# Kintex7_disp_inout_hdmi.net
KiCad netlist of a schematic drawn in EAGLE
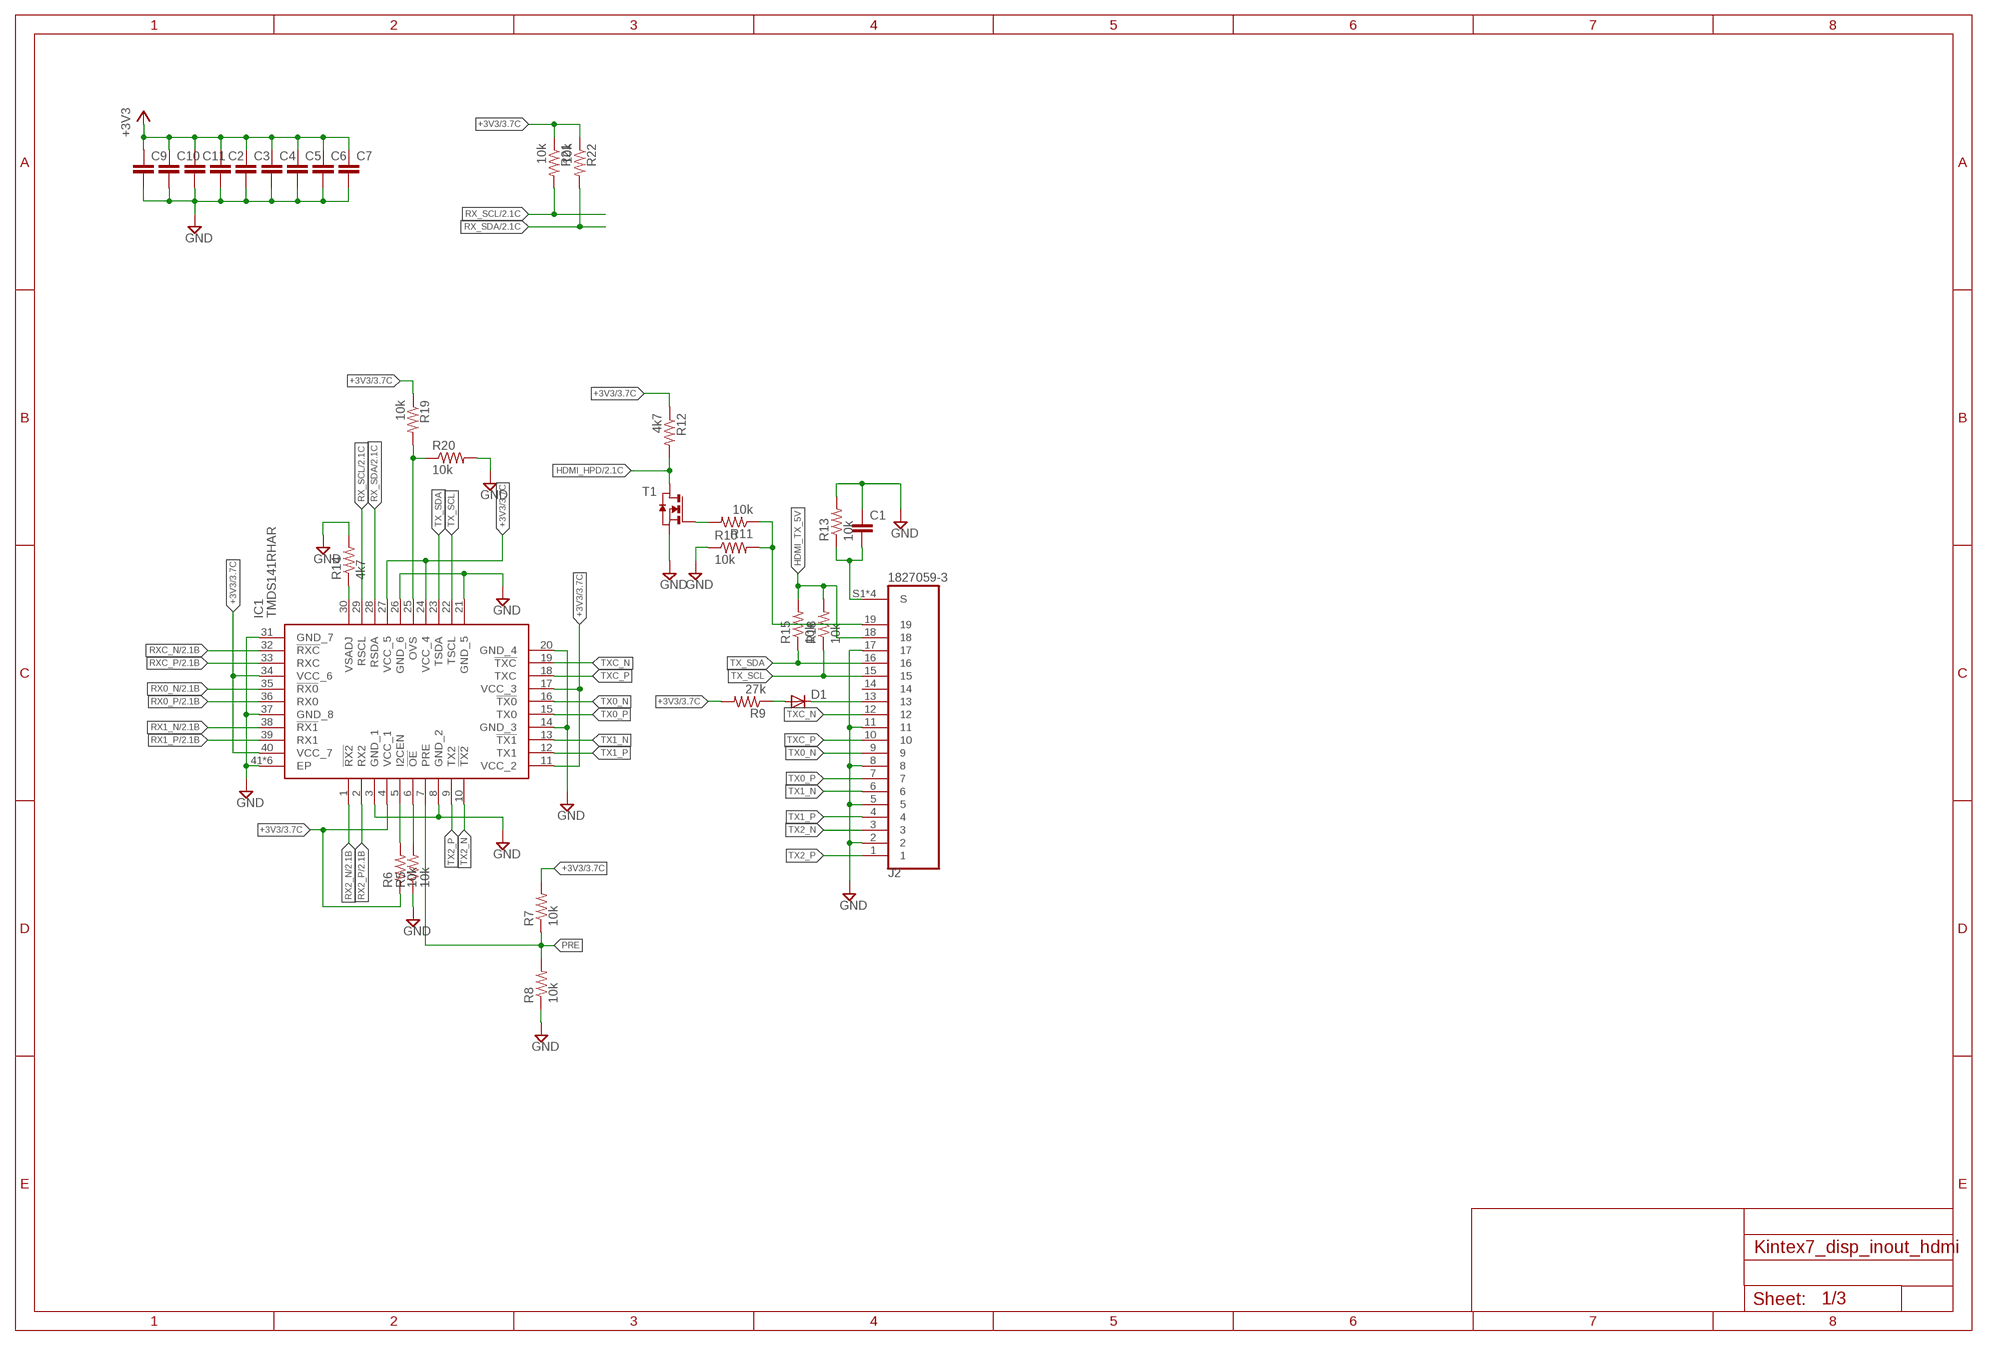
[diagram p0: schematic, sheet 1]
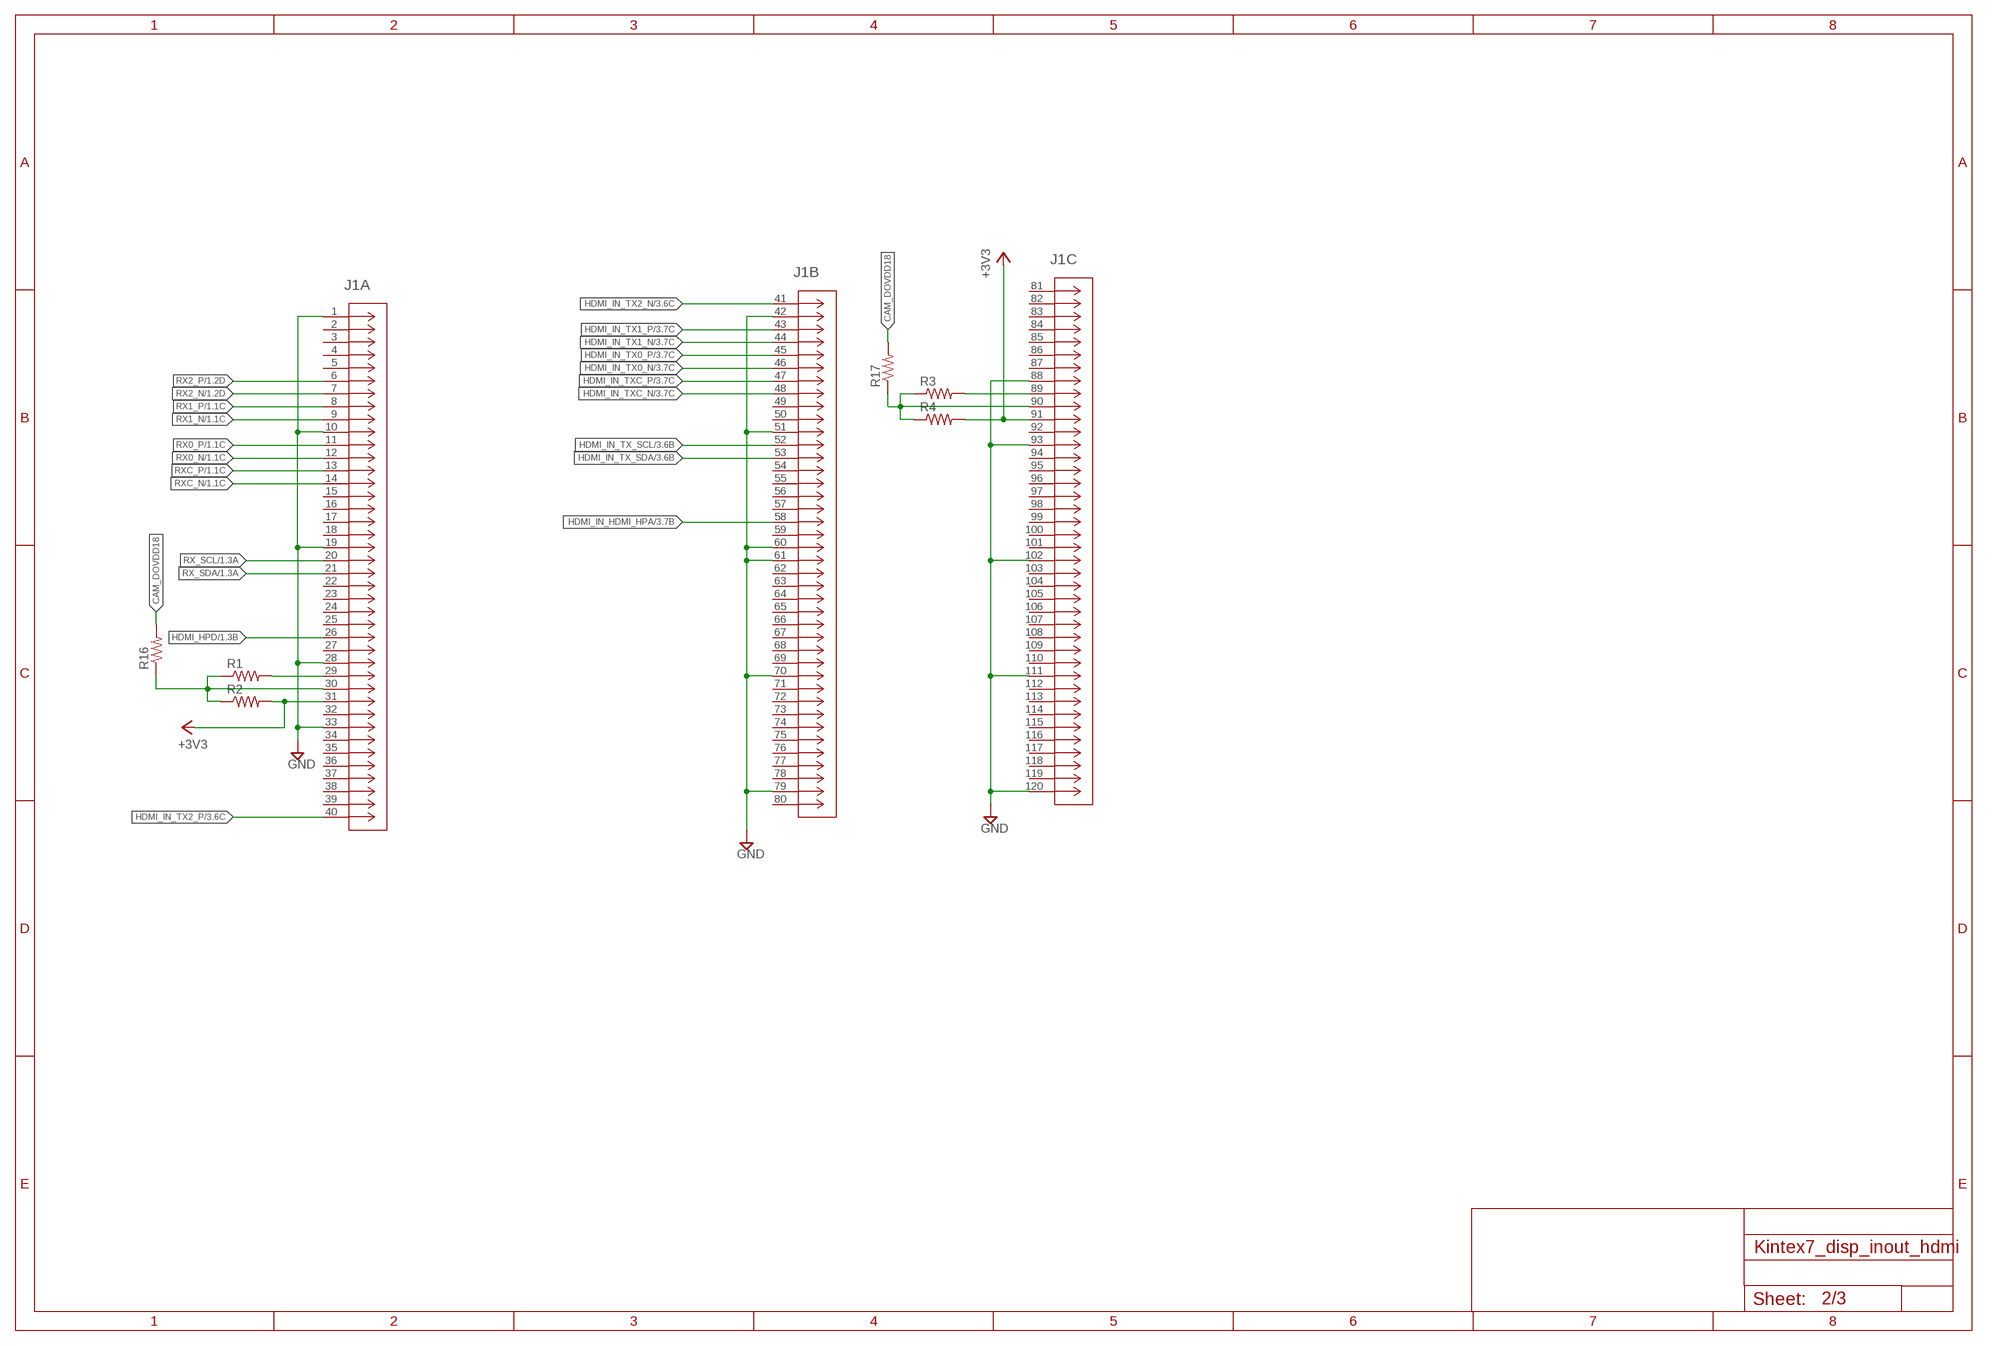
[diagram p1: schematic, sheet 2]
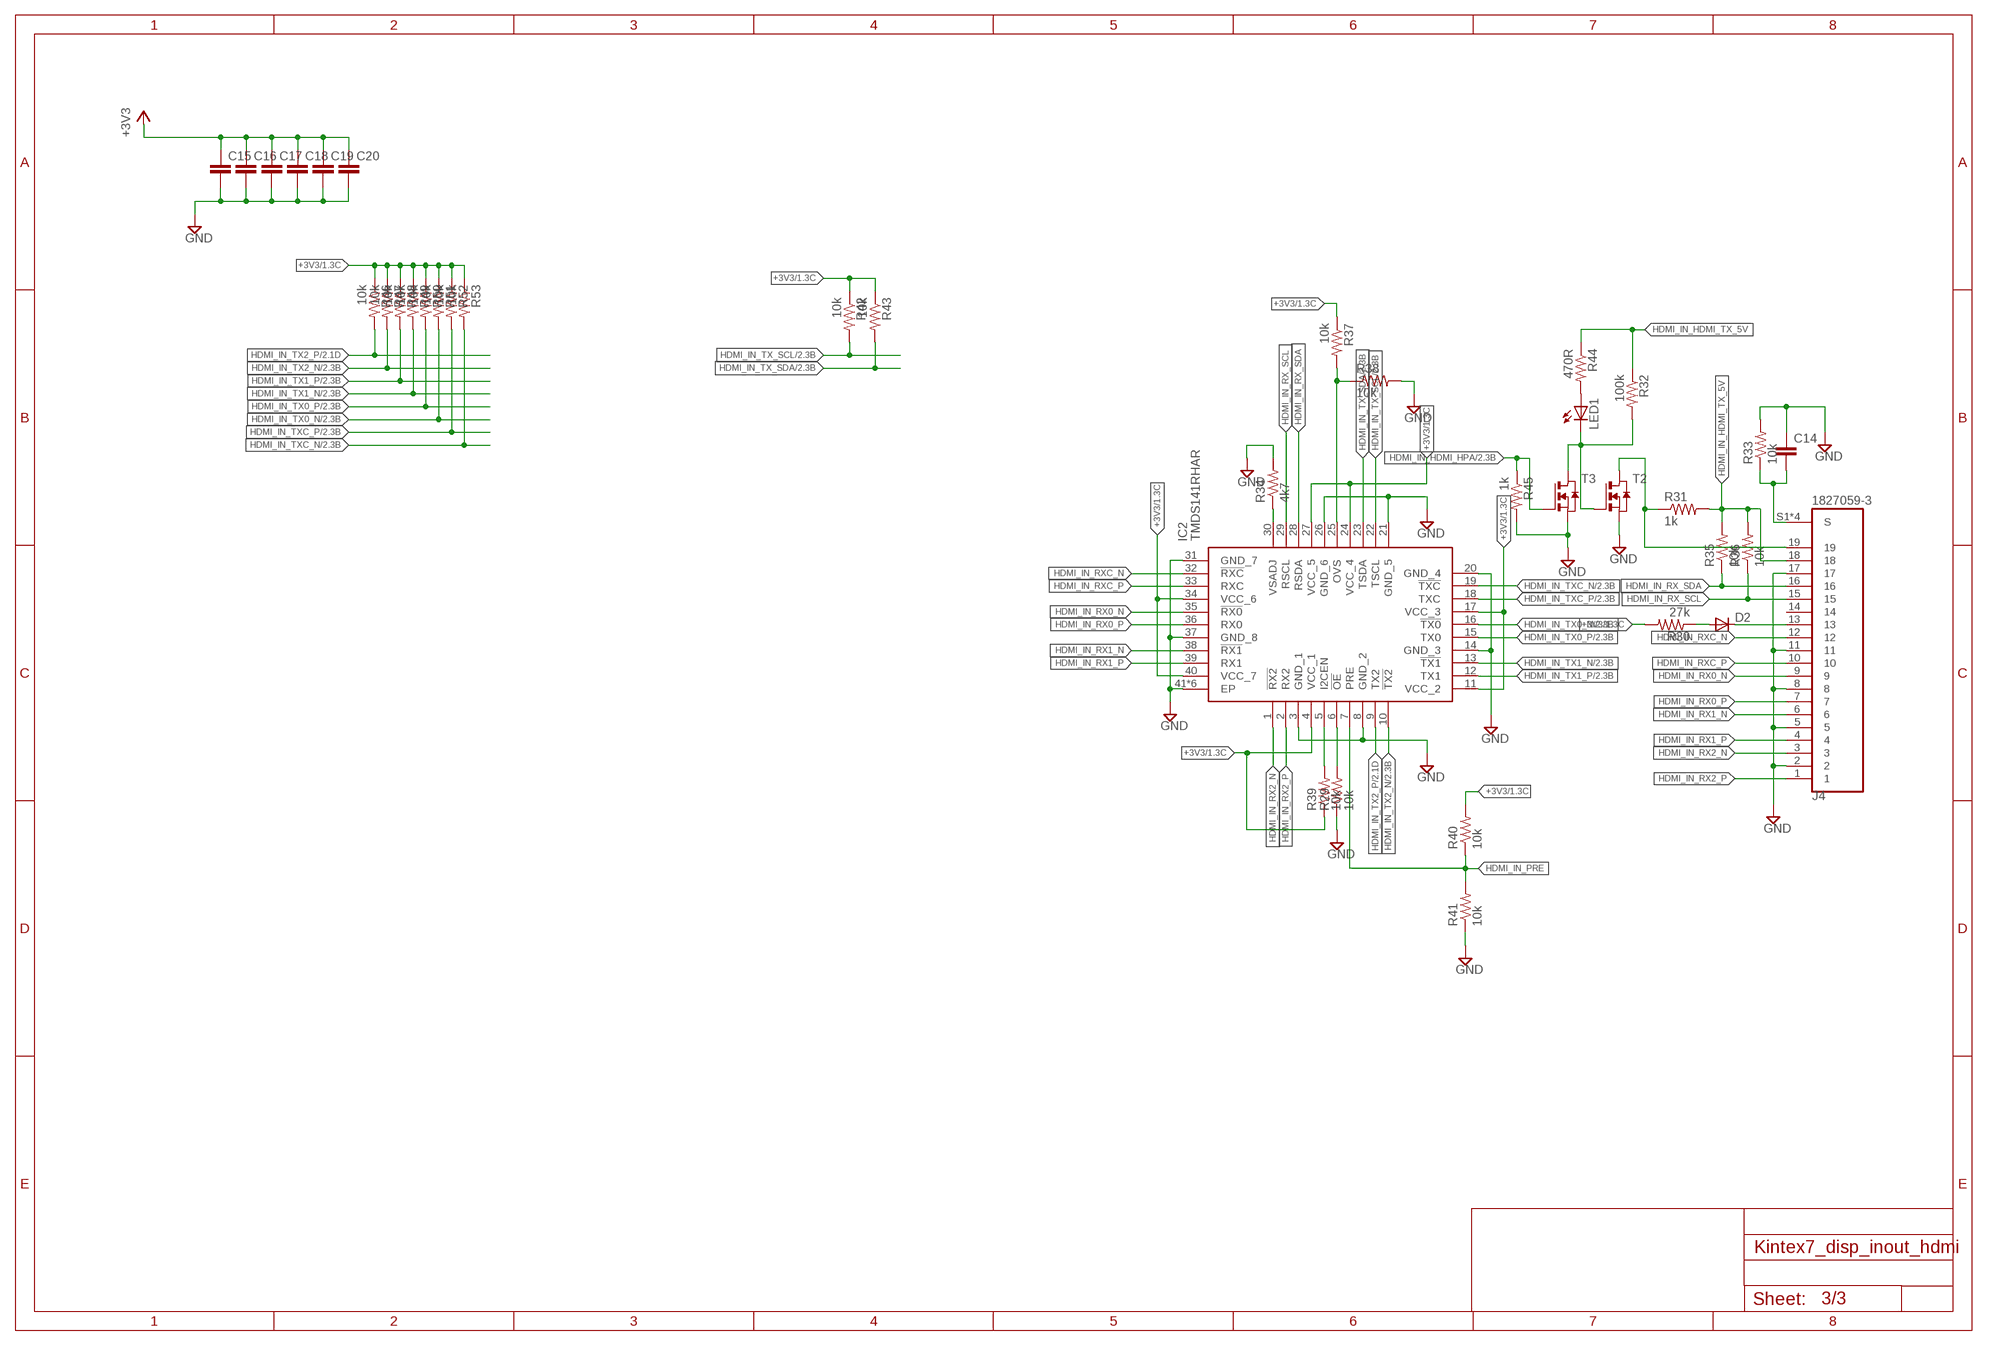
[diagram p2: schematic, sheet 3]

(export (version "E")
  (design (tool "Eeschema 10.0.6"))
  (components
    (comp (ref "C1")
      (value "C-EUC0603")
      (footprint "eagle-import:C0603")
      (libsource (lib "eagle-import") (part "C-EUC0603"))
    )
    (comp (ref "C2")
      (value "C-EUC0603")
      (footprint "eagle-import:C0603")
      (libsource (lib "eagle-import") (part "C-EUC0603"))
    )
    (comp (ref "C3")
      (value "C-EUC0603")
      (footprint "eagle-import:C0603")
      (libsource (lib "eagle-import") (part "C-EUC0603"))
    )
    (comp (ref "C4")
      (value "C-EUC0603")
      (footprint "eagle-import:C0603")
      (libsource (lib "eagle-import") (part "C-EUC0603"))
    )
    (comp (ref "C5")
      (value "C-EUC0603")
      (footprint "eagle-import:C0603")
      (libsource (lib "eagle-import") (part "C-EUC0603"))
    )
    (comp (ref "C6")
      (value "C-EUC0603")
      (footprint "eagle-import:C0603")
      (libsource (lib "eagle-import") (part "C-EUC0603"))
    )
    (comp (ref "C7")
      (value "C-EUC0603")
      (footprint "eagle-import:C0603")
      (libsource (lib "eagle-import") (part "C-EUC0603"))
    )
    (comp (ref "C9")
      (value "C-EUC0603")
      (footprint "eagle-import:C0603")
      (libsource (lib "eagle-import") (part "C-EUC0603"))
    )
    (comp (ref "C10")
      (value "C-EUC0603")
      (footprint "eagle-import:C0603")
      (libsource (lib "eagle-import") (part "C-EUC0603"))
    )
    (comp (ref "C11")
      (value "C-EUC0603")
      (footprint "eagle-import:C0603")
      (libsource (lib "eagle-import") (part "C-EUC0603"))
    )
    (comp (ref "D1")
      (value "DIODE-MINIMELF")
      (footprint "eagle-import:MINIMELF")
      (libsource (lib "eagle-import") (part "DIODE-MINIMELF"))
    )
    (comp (ref "IC1")
      (value "TMDS141RHAR")
      (footprint "eagle-import:QFN50P600X600X100-41N")
      (fields (field (name "RS_PART_NUMBER") "8124195P"))
      (libsource (lib "eagle-import") (part "TMDS141RHAR"))
    )
    (comp (ref "J2")
      (value "1827059-3")
      (footprint "eagle-import:TE_1827059-3")
      (fields (field (name "MF") "TE Connectivity"))
      (libsource (lib "eagle-import") (part "1827059-3"))
    )
    (comp (ref "R5")
      (value "10k")
      (footprint "eagle-import:R0805")
      (libsource (lib "eagle-import") (part "R-US_R0805"))
    )
    (comp (ref "R6")
      (value "10k")
      (footprint "eagle-import:R0805")
      (libsource (lib "eagle-import") (part "R-US_R0805"))
    )
    (comp (ref "R7")
      (value "10k")
      (footprint "eagle-import:R0805")
      (libsource (lib "eagle-import") (part "R-US_R0805"))
    )
    (comp (ref "R8")
      (value "10k")
      (footprint "eagle-import:R0805")
      (libsource (lib "eagle-import") (part "R-US_R0805"))
    )
    (comp (ref "R9")
      (value "27k")
      (footprint "eagle-import:R0805")
      (libsource (lib "eagle-import") (part "R-US_R0805"))
    )
    (comp (ref "R10")
      (value "10k")
      (footprint "eagle-import:R0805")
      (libsource (lib "eagle-import") (part "R-US_R0805"))
    )
    (comp (ref "R11")
      (value "10k")
      (footprint "eagle-import:R0805")
      (libsource (lib "eagle-import") (part "R-US_R0805"))
    )
    (comp (ref "R12")
      (value "4k7")
      (footprint "eagle-import:R0805")
      (libsource (lib "eagle-import") (part "R-US_R0805"))
    )
    (comp (ref "R13")
      (value "10k")
      (footprint "eagle-import:R0805")
      (libsource (lib "eagle-import") (part "R-US_R0805"))
    )
    (comp (ref "R14")
      (value "4k7")
      (footprint "eagle-import:R0805")
      (libsource (lib "eagle-import") (part "R-US_R0805"))
    )
    (comp (ref "R15")
      (value "10k")
      (footprint "eagle-import:R0805")
      (libsource (lib "eagle-import") (part "R-US_R0805"))
    )
    (comp (ref "R18")
      (value "10k")
      (footprint "eagle-import:R0805")
      (libsource (lib "eagle-import") (part "R-US_R0805"))
    )
    (comp (ref "R19")
      (value "10k")
      (footprint "eagle-import:R0805")
      (libsource (lib "eagle-import") (part "R-US_R0805"))
    )
    (comp (ref "R20")
      (value "10k")
      (footprint "eagle-import:R0805")
      (libsource (lib "eagle-import") (part "R-US_R0805"))
    )
    (comp (ref "R21")
      (value "10k")
      (footprint "eagle-import:R0805")
      (libsource (lib "eagle-import") (part "R-US_R0805"))
    )
    (comp (ref "R22")
      (value "10k")
      (footprint "eagle-import:R0805")
      (libsource (lib "eagle-import") (part "R-US_R0805"))
    )
    (comp (ref "T1")
      (value "NMOSSOT23")
      (footprint "eagle-import:SOT-23")
      (libsource (lib "eagle-import") (part "NMOSSOT23"))
    )
    (comp (ref "C14")
      (value "C-EUC0603")
      (footprint "eagle-import:C0603")
      (libsource (lib "eagle-import") (part "C-EUC0603"))
    )
    (comp (ref "C15")
      (value "C-EUC0603")
      (footprint "eagle-import:C0603")
      (libsource (lib "eagle-import") (part "C-EUC0603"))
    )
    (comp (ref "C16")
      (value "C-EUC0603")
      (footprint "eagle-import:C0603")
      (libsource (lib "eagle-import") (part "C-EUC0603"))
    )
    (comp (ref "C17")
      (value "C-EUC0603")
      (footprint "eagle-import:C0603")
      (libsource (lib "eagle-import") (part "C-EUC0603"))
    )
    (comp (ref "C18")
      (value "C-EUC0603")
      (footprint "eagle-import:C0603")
      (libsource (lib "eagle-import") (part "C-EUC0603"))
    )
    (comp (ref "C19")
      (value "C-EUC0603")
      (footprint "eagle-import:C0603")
      (libsource (lib "eagle-import") (part "C-EUC0603"))
    )
    (comp (ref "C20")
      (value "C-EUC0603")
      (footprint "eagle-import:C0603")
      (libsource (lib "eagle-import") (part "C-EUC0603"))
    )
    (comp (ref "D2")
      (value "DIODE-MINIMELF")
      (footprint "eagle-import:MINIMELF")
      (libsource (lib "eagle-import") (part "DIODE-MINIMELF"))
    )
    (comp (ref "IC2")
      (value "TMDS141RHAR")
      (footprint "eagle-import:QFN50P600X600X100-41N")
      (fields (field (name "RS_PART_NUMBER") "8124195P"))
      (libsource (lib "eagle-import") (part "TMDS141RHAR"))
    )
    (comp (ref "J4")
      (value "1827059-3")
      (footprint "eagle-import:TE_1827059-3")
      (fields (field (name "MF") "TE Connectivity"))
      (libsource (lib "eagle-import") (part "1827059-3"))
    )
    (comp (ref "LED1")
      (value "LEDCHIPLED_0603")
      (footprint "eagle-import:CHIPLED_0603")
      (libsource (lib "eagle-import") (part "LEDCHIPLED_0603"))
    )
    (comp (ref "R29")
      (value "10k")
      (footprint "eagle-import:R0805")
      (libsource (lib "eagle-import") (part "R-US_R0805"))
    )
    (comp (ref "R30")
      (value "27k")
      (footprint "eagle-import:R0805")
      (libsource (lib "eagle-import") (part "R-US_R0805"))
    )
    (comp (ref "R31")
      (value "1k")
      (footprint "eagle-import:R0805")
      (libsource (lib "eagle-import") (part "R-US_R0805"))
    )
    (comp (ref "R32")
      (value "100k")
      (footprint "eagle-import:R0805")
      (libsource (lib "eagle-import") (part "R-US_R0805"))
    )
    (comp (ref "R33")
      (value "10k")
      (footprint "eagle-import:R0805")
      (libsource (lib "eagle-import") (part "R-US_R0805"))
    )
    (comp (ref "R34")
      (value "4k7")
      (footprint "eagle-import:R0805")
      (libsource (lib "eagle-import") (part "R-US_R0805"))
    )
    (comp (ref "R35")
      (value "10k")
      (footprint "eagle-import:R0805")
      (libsource (lib "eagle-import") (part "R-US_R0805"))
    )
    (comp (ref "R36")
      (value "10k")
      (footprint "eagle-import:R0805")
      (libsource (lib "eagle-import") (part "R-US_R0805"))
    )
    (comp (ref "R37")
      (value "10k")
      (footprint "eagle-import:R0805")
      (libsource (lib "eagle-import") (part "R-US_R0805"))
    )
    (comp (ref "R38")
      (value "10k")
      (footprint "eagle-import:R0805")
      (libsource (lib "eagle-import") (part "R-US_R0805"))
    )
    (comp (ref "R39")
      (value "10k")
      (footprint "eagle-import:R0805")
      (libsource (lib "eagle-import") (part "R-US_R0805"))
    )
    (comp (ref "R40")
      (value "10k")
      (footprint "eagle-import:R0805")
      (libsource (lib "eagle-import") (part "R-US_R0805"))
    )
    (comp (ref "R41")
      (value "10k")
      (footprint "eagle-import:R0805")
      (libsource (lib "eagle-import") (part "R-US_R0805"))
    )
    (comp (ref "R42")
      (value "10k")
      (footprint "eagle-import:R0805")
      (libsource (lib "eagle-import") (part "R-US_R0805"))
    )
    (comp (ref "R43")
      (value "10k")
      (footprint "eagle-import:R0805")
      (libsource (lib "eagle-import") (part "R-US_R0805"))
    )
    (comp (ref "R44")
      (value "470R")
      (footprint "eagle-import:R0805")
      (libsource (lib "eagle-import") (part "R-US_R0805"))
    )
    (comp (ref "R45")
      (value "1k")
      (footprint "eagle-import:R0805")
      (libsource (lib "eagle-import") (part "R-US_R0805"))
    )
    (comp (ref "R46")
      (value "10k")
      (footprint "eagle-import:R0805")
      (libsource (lib "eagle-import") (part "R-US_R0805"))
    )
    (comp (ref "R47")
      (value "10k")
      (footprint "eagle-import:R0805")
      (libsource (lib "eagle-import") (part "R-US_R0805"))
    )
    (comp (ref "R48")
      (value "10k")
      (footprint "eagle-import:R0805")
      (libsource (lib "eagle-import") (part "R-US_R0805"))
    )
    (comp (ref "R49")
      (value "10k")
      (footprint "eagle-import:R0805")
      (libsource (lib "eagle-import") (part "R-US_R0805"))
    )
    (comp (ref "R50")
      (value "10k")
      (footprint "eagle-import:R0805")
      (libsource (lib "eagle-import") (part "R-US_R0805"))
    )
    (comp (ref "R51")
      (value "10k")
      (footprint "eagle-import:R0805")
      (libsource (lib "eagle-import") (part "R-US_R0805"))
    )
    (comp (ref "R52")
      (value "10k")
      (footprint "eagle-import:R0805")
      (libsource (lib "eagle-import") (part "R-US_R0805"))
    )
    (comp (ref "R53")
      (value "10k")
      (footprint "eagle-import:R0805")
      (libsource (lib "eagle-import") (part "R-US_R0805"))
    )
    (comp (ref "T2")
      (value "NMOSSOT23")
      (footprint "eagle-import:SOT-23")
      (libsource (lib "eagle-import") (part "NMOSSOT23"))
    )
    (comp (ref "T3")
      (value "NMOSSOT23")
      (footprint "eagle-import:SOT-23")
      (libsource (lib "eagle-import") (part "NMOSSOT23"))
    )
    (comp (ref "J1")
      (value "5177985-5")
      (footprint "eagle-import:CONN_5177985-5")
      (libsource (lib "eagle-import") (part "5177985-5"))
    )
    (comp (ref "R1")
      (value "R-US_R0805")
      (footprint "eagle-import:R0805")
      (libsource (lib "eagle-import") (part "R-US_R0805"))
    )
    (comp (ref "R2")
      (value "R-US_R0805")
      (footprint "eagle-import:R0805")
      (libsource (lib "eagle-import") (part "R-US_R0805"))
    )
    (comp (ref "R3")
      (value "R-US_R0805")
      (footprint "eagle-import:R0805")
      (libsource (lib "eagle-import") (part "R-US_R0805"))
    )
    (comp (ref "R4")
      (value "R-US_R0805")
      (footprint "eagle-import:R0805")
      (libsource (lib "eagle-import") (part "R-US_R0805"))
    )
    (comp (ref "R16")
      (value "R-US_R0805")
      (footprint "eagle-import:R0805")
      (libsource (lib "eagle-import") (part "R-US_R0805"))
    )
    (comp (ref "R17")
      (value "R-US_R0805")
      (footprint "eagle-import:R0805")
      (libsource (lib "eagle-import") (part "R-US_R0805"))
    )
  )
  (nets
    (net (code "1") (name "+3V3") (class "Default")
      (node (ref "C10") (pin "1") (pinfunction "1_1") (pintype "passive"))
      (node (ref "C11") (pin "1") (pinfunction "1_1") (pintype "passive"))
      (node (ref "C15") (pin "1") (pinfunction "1_1") (pintype "passive"))
      (node (ref "C16") (pin "1") (pinfunction "1_1") (pintype "passive"))
      (node (ref "C17") (pin "1") (pinfunction "1_1") (pintype "passive"))
      (node (ref "C18") (pin "1") (pinfunction "1_1") (pintype "passive"))
      (node (ref "C19") (pin "1") (pinfunction "1_1") (pintype "passive"))
      (node (ref "C2") (pin "1") (pinfunction "1_1") (pintype "passive"))
      (node (ref "C20") (pin "1") (pinfunction "1_1") (pintype "passive"))
      (node (ref "C3") (pin "1") (pinfunction "1_1") (pintype "passive"))
      (node (ref "C4") (pin "1") (pinfunction "1_1") (pintype "passive"))
      (node (ref "C5") (pin "1") (pinfunction "1_1") (pintype "passive"))
      (node (ref "C6") (pin "1") (pinfunction "1_1") (pintype "passive"))
      (node (ref "C7") (pin "1") (pinfunction "1_1") (pintype "passive"))
      (node (ref "C9") (pin "1") (pinfunction "1_1") (pintype "passive"))
      (node (ref "IC1") (pin "11") (pinfunction "VCC_2_11") (pintype "bidirectional"))
      (node (ref "IC1") (pin "17") (pinfunction "VCC_3_17") (pintype "bidirectional"))
      (node (ref "IC1") (pin "24") (pinfunction "VCC_4_24") (pintype "bidirectional"))
      (node (ref "IC1") (pin "27") (pinfunction "VCC_5_27") (pintype "bidirectional"))
      (node (ref "IC1") (pin "34") (pinfunction "VCC_6_34") (pintype "bidirectional"))
      (node (ref "IC1") (pin "4") (pinfunction "VCC_1_4") (pintype "bidirectional"))
      (node (ref "IC1") (pin "40") (pinfunction "VCC_7_40") (pintype "bidirectional"))
      (node (ref "IC2") (pin "11") (pinfunction "VCC_2_11") (pintype "bidirectional"))
      (node (ref "IC2") (pin "17") (pinfunction "VCC_3_17") (pintype "bidirectional"))
      (node (ref "IC2") (pin "24") (pinfunction "VCC_4_24") (pintype "bidirectional"))
      (node (ref "IC2") (pin "27") (pinfunction "VCC_5_27") (pintype "bidirectional"))
      (node (ref "IC2") (pin "34") (pinfunction "VCC_6_34") (pintype "bidirectional"))
      (node (ref "IC2") (pin "4") (pinfunction "VCC_1_4") (pintype "bidirectional"))
      (node (ref "IC2") (pin "40") (pinfunction "VCC_7_40") (pintype "bidirectional"))
      (node (ref "J1") (pin "31") (pinfunction "31_31") (pintype "passive"))
      (node (ref "J1") (pin "91") (pinfunction "91_91") (pintype "passive"))
      (node (ref "R12") (pin "1") (pinfunction "1_1") (pintype "passive"))
      (node (ref "R19") (pin "1") (pinfunction "1_1") (pintype "passive"))
      (node (ref "R2") (pin "2") (pinfunction "2_2") (pintype "passive"))
      (node (ref "R21") (pin "1") (pinfunction "1_1") (pintype "passive"))
      (node (ref "R22") (pin "1") (pinfunction "1_1") (pintype "passive"))
      (node (ref "R30") (pin "2") (pinfunction "2_2") (pintype "passive"))
      (node (ref "R37") (pin "1") (pinfunction "1_1") (pintype "passive"))
      (node (ref "R39") (pin "1") (pinfunction "1_1") (pintype "passive"))
      (node (ref "R4") (pin "2") (pinfunction "2_2") (pintype "passive"))
      (node (ref "R40") (pin "2") (pinfunction "2_2") (pintype "passive"))
      (node (ref "R42") (pin "1") (pinfunction "1_1") (pintype "passive"))
      (node (ref "R43") (pin "1") (pinfunction "1_1") (pintype "passive"))
      (node (ref "R46") (pin "1") (pinfunction "1_1") (pintype "passive"))
      (node (ref "R47") (pin "1") (pinfunction "1_1") (pintype "passive"))
      (node (ref "R48") (pin "1") (pinfunction "1_1") (pintype "passive"))
      (node (ref "R49") (pin "1") (pinfunction "1_1") (pintype "passive"))
      (node (ref "R50") (pin "1") (pinfunction "1_1") (pintype "passive"))
      (node (ref "R51") (pin "1") (pinfunction "1_1") (pintype "passive"))
      (node (ref "R52") (pin "1") (pinfunction "1_1") (pintype "passive"))
      (node (ref "R53") (pin "1") (pinfunction "1_1") (pintype "passive"))
      (node (ref "R6") (pin "1") (pinfunction "1_1") (pintype "passive"))
      (node (ref "R7") (pin "2") (pinfunction "2_2") (pintype "passive"))
      (node (ref "R9") (pin "2") (pinfunction "2_2") (pintype "passive"))
    )
    (net (code "2") (name "CAM_DOVDD18") (class "Default")
      (node (ref "R16") (pin "2") (pinfunction "2_2") (pintype "passive"))
      (node (ref "R17") (pin "2") (pinfunction "2_2") (pintype "passive"))
    )
    (net (code "3") (name "GND") (class "Default")
      (node (ref "C1") (pin "1") (pinfunction "1_1") (pintype "passive"))
      (node (ref "C10") (pin "2") (pinfunction "2_2") (pintype "passive"))
      (node (ref "C11") (pin "2") (pinfunction "2_2") (pintype "passive"))
      (node (ref "C14") (pin "1") (pinfunction "1_1") (pintype "passive"))
      (node (ref "C15") (pin "2") (pinfunction "2_2") (pintype "passive"))
      (node (ref "C16") (pin "2") (pinfunction "2_2") (pintype "passive"))
      (node (ref "C17") (pin "2") (pinfunction "2_2") (pintype "passive"))
      (node (ref "C18") (pin "2") (pinfunction "2_2") (pintype "passive"))
      (node (ref "C19") (pin "2") (pinfunction "2_2") (pintype "passive"))
      (node (ref "C2") (pin "2") (pinfunction "2_2") (pintype "passive"))
      (node (ref "C20") (pin "2") (pinfunction "2_2") (pintype "passive"))
      (node (ref "C3") (pin "2") (pinfunction "2_2") (pintype "passive"))
      (node (ref "C4") (pin "2") (pinfunction "2_2") (pintype "passive"))
      (node (ref "C5") (pin "2") (pinfunction "2_2") (pintype "passive"))
      (node (ref "C6") (pin "2") (pinfunction "2_2") (pintype "passive"))
      (node (ref "C7") (pin "2") (pinfunction "2_2") (pintype "passive"))
      (node (ref "C9") (pin "2") (pinfunction "2_2") (pintype "passive"))
      (node (ref "IC1") (pin "14") (pinfunction "GND_3_14") (pintype "bidirectional"))
      (node (ref "IC1") (pin "20") (pinfunction "GND_4_20") (pintype "bidirectional"))
      (node (ref "IC1") (pin "21") (pinfunction "GND_5_21") (pintype "bidirectional"))
      (node (ref "IC1") (pin "26") (pinfunction "GND_6_26") (pintype "bidirectional"))
      (node (ref "IC1") (pin "3") (pinfunction "GND_1_3") (pintype "bidirectional"))
      (node (ref "IC1") (pin "31") (pinfunction "GND_7_31") (pintype "bidirectional"))
      (node (ref "IC1") (pin "37") (pinfunction "GND_8_37") (pintype "bidirectional"))
      (node (ref "IC1") (pin "41") (pinfunction "EP_41") (pintype "bidirectional"))
      (node (ref "IC1") (pin "8") (pinfunction "GND_2_8") (pintype "bidirectional"))
      (node (ref "IC1") (pin "P$1") (pinfunction "EP_P$1") (pintype "bidirectional"))
      (node (ref "IC1") (pin "P$2") (pinfunction "EP_P$2") (pintype "bidirectional"))
      (node (ref "IC1") (pin "P$3") (pinfunction "EP_P$3") (pintype "bidirectional"))
      (node (ref "IC1") (pin "P$4") (pinfunction "EP_P$4") (pintype "bidirectional"))
      (node (ref "IC1") (pin "P$5") (pinfunction "EP_P$5") (pintype "bidirectional"))
      (node (ref "IC2") (pin "14") (pinfunction "GND_3_14") (pintype "bidirectional"))
      (node (ref "IC2") (pin "20") (pinfunction "GND_4_20") (pintype "bidirectional"))
      (node (ref "IC2") (pin "21") (pinfunction "GND_5_21") (pintype "bidirectional"))
      (node (ref "IC2") (pin "26") (pinfunction "GND_6_26") (pintype "bidirectional"))
      (node (ref "IC2") (pin "3") (pinfunction "GND_1_3") (pintype "bidirectional"))
      (node (ref "IC2") (pin "31") (pinfunction "GND_7_31") (pintype "bidirectional"))
      (node (ref "IC2") (pin "37") (pinfunction "GND_8_37") (pintype "bidirectional"))
      (node (ref "IC2") (pin "41") (pinfunction "EP_41") (pintype "bidirectional"))
      (node (ref "IC2") (pin "8") (pinfunction "GND_2_8") (pintype "bidirectional"))
      (node (ref "IC2") (pin "P$1") (pinfunction "EP_P$1") (pintype "bidirectional"))
      (node (ref "IC2") (pin "P$2") (pinfunction "EP_P$2") (pintype "bidirectional"))
      (node (ref "IC2") (pin "P$3") (pinfunction "EP_P$3") (pintype "bidirectional"))
      (node (ref "IC2") (pin "P$4") (pinfunction "EP_P$4") (pintype "bidirectional"))
      (node (ref "IC2") (pin "P$5") (pinfunction "EP_P$5") (pintype "bidirectional"))
      (node (ref "J1") (pin "1") (pinfunction "1_1") (pintype "passive"))
      (node (ref "J1") (pin "10") (pinfunction "10_10") (pintype "passive"))
      (node (ref "J1") (pin "102") (pinfunction "102_102") (pintype "passive"))
      (node (ref "J1") (pin "111") (pinfunction "111_111") (pintype "passive"))
      (node (ref "J1") (pin "120") (pinfunction "120_120") (pintype "passive"))
      (node (ref "J1") (pin "19") (pinfunction "19_19") (pintype "passive"))
      (node (ref "J1") (pin "28") (pinfunction "28_28") (pintype "passive"))
      (node (ref "J1") (pin "33") (pinfunction "33_33") (pintype "passive"))
      (node (ref "J1") (pin "42") (pinfunction "42_42") (pintype "passive"))
      (node (ref "J1") (pin "51") (pinfunction "51_51") (pintype "passive"))
      (node (ref "J1") (pin "60") (pinfunction "60_60") (pintype "passive"))
      (node (ref "J1") (pin "61") (pinfunction "61_61") (pintype "passive"))
      (node (ref "J1") (pin "70") (pinfunction "70_70") (pintype "passive"))
      (node (ref "J1") (pin "79") (pinfunction "79_79") (pintype "passive"))
      (node (ref "J1") (pin "88") (pinfunction "88_88") (pintype "passive"))
      (node (ref "J1") (pin "93") (pinfunction "93_93") (pintype "passive"))
      (node (ref "J2") (pin "11") (pinfunction "11_11") (pintype "passive"))
      (node (ref "J2") (pin "17") (pinfunction "17_17") (pintype "passive"))
      (node (ref "J2") (pin "2") (pinfunction "2_2") (pintype "passive"))
      (node (ref "J2") (pin "5") (pinfunction "5_5") (pintype "passive"))
      (node (ref "J2") (pin "8") (pinfunction "8_8") (pintype "passive"))
      (node (ref "J4") (pin "11") (pinfunction "11_11") (pintype "passive"))
      (node (ref "J4") (pin "17") (pinfunction "17_17") (pintype "passive"))
      (node (ref "J4") (pin "2") (pinfunction "2_2") (pintype "passive"))
      (node (ref "J4") (pin "5") (pinfunction "5_5") (pintype "passive"))
      (node (ref "J4") (pin "8") (pinfunction "8_8") (pintype "passive"))
      (node (ref "R10") (pin "1") (pinfunction "1_1") (pintype "passive"))
      (node (ref "R13") (pin "2") (pinfunction "2_2") (pintype "passive"))
      (node (ref "R14") (pin "2") (pinfunction "2_2") (pintype "passive"))
      (node (ref "R20") (pin "2") (pinfunction "2_2") (pintype "passive"))
      (node (ref "R29") (pin "1") (pinfunction "1_1") (pintype "passive"))
      (node (ref "R33") (pin "2") (pinfunction "2_2") (pintype "passive"))
      (node (ref "R34") (pin "2") (pinfunction "2_2") (pintype "passive"))
      (node (ref "R38") (pin "2") (pinfunction "2_2") (pintype "passive"))
      (node (ref "R41") (pin "1") (pinfunction "1_1") (pintype "passive"))
      (node (ref "R45") (pin "2") (pinfunction "2_2") (pintype "passive"))
      (node (ref "R5") (pin "1") (pinfunction "1_1") (pintype "passive"))
      (node (ref "R8") (pin "1") (pinfunction "1_1") (pintype "passive"))
      (node (ref "T1") (pin "2") (pinfunction "S_2") (pintype "passive"))
      (node (ref "T2") (pin "2") (pinfunction "S_2") (pintype "passive"))
      (node (ref "T3") (pin "2") (pinfunction "S_2") (pintype "passive"))
    )
    (net (code "4") (name "HDMI_HPD") (class "Default")
      (node (ref "J1") (pin "26") (pinfunction "26_26") (pintype "passive"))
      (node (ref "R12") (pin "2") (pinfunction "2_2") (pintype "passive"))
      (node (ref "T1") (pin "1") (pinfunction "D_1") (pintype "passive"))
    )
    (net (code "5") (name "HDMI_IN_HDMI_HPA") (class "Default")
      (node (ref "J1") (pin "58") (pinfunction "58_58") (pintype "passive"))
      (node (ref "R45") (pin "1") (pinfunction "1_1") (pintype "passive"))
      (node (ref "T3") (pin "3") (pinfunction "G_3") (pintype "passive"))
    )
    (net (code "6") (name "HDMI_IN_HDMI_TX_5V") (class "Default")
      (node (ref "J4") (pin "18") (pinfunction "18_18") (pintype "passive"))
      (node (ref "R31") (pin "2") (pinfunction "2_2") (pintype "passive"))
      (node (ref "R32") (pin "1") (pinfunction "1_1") (pintype "passive"))
      (node (ref "R35") (pin "2") (pinfunction "2_2") (pintype "passive"))
      (node (ref "R36") (pin "2") (pinfunction "2_2") (pintype "passive"))
      (node (ref "R44") (pin "1") (pinfunction "1_1") (pintype "passive"))
    )
    (net (code "7") (name "HDMI_IN_PRE") (class "Default")
      (node (ref "IC2") (pin "7") (pinfunction "PRE_7") (pintype "bidirectional"))
      (node (ref "R40") (pin "1") (pinfunction "1_1") (pintype "passive"))
      (node (ref "R41") (pin "2") (pinfunction "2_2") (pintype "passive"))
    )
    (net (code "8") (name "HDMI_IN_RX0_N") (class "Default")
      (node (ref "IC2") (pin "35") (pinfunction "~{RX0}_35") (pintype "bidirectional"))
      (node (ref "J4") (pin "9") (pinfunction "9_9") (pintype "passive"))
    )
    (net (code "9") (name "HDMI_IN_RX0_P") (class "Default")
      (node (ref "IC2") (pin "36") (pinfunction "RX0_36") (pintype "bidirectional"))
      (node (ref "J4") (pin "7") (pinfunction "7_7") (pintype "passive"))
    )
    (net (code "10") (name "HDMI_IN_RX1_N") (class "Default")
      (node (ref "IC2") (pin "38") (pinfunction "~{RX1}_38") (pintype "bidirectional"))
      (node (ref "J4") (pin "6") (pinfunction "6_6") (pintype "passive"))
    )
    (net (code "11") (name "HDMI_IN_RX1_P") (class "Default")
      (node (ref "IC2") (pin "39") (pinfunction "RX1_39") (pintype "bidirectional"))
      (node (ref "J4") (pin "4") (pinfunction "4_4") (pintype "passive"))
    )
    (net (code "12") (name "HDMI_IN_RX2_N") (class "Default")
      (node (ref "IC2") (pin "1") (pinfunction "~{RX2}_1") (pintype "bidirectional"))
      (node (ref "J4") (pin "3") (pinfunction "3_3") (pintype "passive"))
    )
    (net (code "13") (name "HDMI_IN_RX2_P") (class "Default")
      (node (ref "IC2") (pin "2") (pinfunction "RX2_2") (pintype "bidirectional"))
      (node (ref "J4") (pin "1") (pinfunction "1_1") (pintype "passive"))
    )
    (net (code "14") (name "HDMI_IN_RXC_N") (class "Default")
      (node (ref "IC2") (pin "32") (pinfunction "~{RXC}_32") (pintype "bidirectional"))
      (node (ref "J4") (pin "12") (pinfunction "12_12") (pintype "passive"))
    )
    (net (code "15") (name "HDMI_IN_RXC_P") (class "Default")
      (node (ref "IC2") (pin "33") (pinfunction "RXC_33") (pintype "bidirectional"))
      (node (ref "J4") (pin "10") (pinfunction "10_10") (pintype "passive"))
    )
    (net (code "16") (name "HDMI_IN_RX_SCL") (class "Default")
      (node (ref "IC2") (pin "29") (pinfunction "RSCL_29") (pintype "bidirectional"))
      (node (ref "J4") (pin "15") (pinfunction "15_15") (pintype "passive"))
      (node (ref "R36") (pin "1") (pinfunction "1_1") (pintype "passive"))
    )
    (net (code "17") (name "HDMI_IN_RX_SDA") (class "Default")
      (node (ref "IC2") (pin "28") (pinfunction "RSDA_28") (pintype "bidirectional"))
      (node (ref "J4") (pin "16") (pinfunction "16_16") (pintype "passive"))
      (node (ref "R35") (pin "1") (pinfunction "1_1") (pintype "passive"))
    )
    (net (code "18") (name "HDMI_IN_TX0_N") (class "Default")
      (node (ref "IC2") (pin "16") (pinfunction "~{TX0}_16") (pintype "bidirectional"))
      (node (ref "J1") (pin "46") (pinfunction "46_46") (pintype "passive"))
      (node (ref "R51") (pin "2") (pinfunction "2_2") (pintype "passive"))
    )
    (net (code "19") (name "HDMI_IN_TX0_P") (class "Default")
      (node (ref "IC2") (pin "15") (pinfunction "TX0_15") (pintype "bidirectional"))
      (node (ref "J1") (pin "45") (pinfunction "45_45") (pintype "passive"))
      (node (ref "R50") (pin "2") (pinfunction "2_2") (pintype "passive"))
    )
    (net (code "20") (name "HDMI_IN_TX1_N") (class "Default")
      (node (ref "IC2") (pin "13") (pinfunction "~{TX1}_13") (pintype "bidirectional"))
      (node (ref "J1") (pin "44") (pinfunction "44_44") (pintype "passive"))
      (node (ref "R49") (pin "2") (pinfunction "2_2") (pintype "passive"))
    )
    (net (code "21") (name "HDMI_IN_TX1_P") (class "Default")
      (node (ref "IC2") (pin "12") (pinfunction "TX1_12") (pintype "bidirectional"))
      (node (ref "J1") (pin "43") (pinfunction "43_43") (pintype "passive"))
      (node (ref "R48") (pin "2") (pinfunction "2_2") (pintype "passive"))
    )
    (net (code "22") (name "HDMI_IN_TX2_N") (class "Default")
      (node (ref "IC2") (pin "10") (pinfunction "~{TX2}_10") (pintype "bidirectional"))
      (node (ref "J1") (pin "41") (pinfunction "41_41") (pintype "passive"))
      (node (ref "R47") (pin "2") (pinfunction "2_2") (pintype "passive"))
    )
    (net (code "23") (name "HDMI_IN_TX2_P") (class "Default")
      (node (ref "IC2") (pin "9") (pinfunction "TX2_9") (pintype "bidirectional"))
      (node (ref "J1") (pin "40") (pinfunction "40_40") (pintype "passive"))
      (node (ref "R46") (pin "2") (pinfunction "2_2") (pintype "passive"))
    )
    (net (code "24") (name "HDMI_IN_TXC_N") (class "Default")
      (node (ref "IC2") (pin "19") (pinfunction "~{TXC}_19") (pintype "bidirectional"))
      (node (ref "J1") (pin "48") (pinfunction "48_48") (pintype "passive"))
      (node (ref "R53") (pin "2") (pinfunction "2_2") (pintype "passive"))
    )
    (net (code "25") (name "HDMI_IN_TXC_P") (class "Default")
      (node (ref "IC2") (pin "18") (pinfunction "TXC_18") (pintype "bidirectional"))
      (node (ref "J1") (pin "47") (pinfunction "47_47") (pintype "passive"))
      (node (ref "R52") (pin "2") (pinfunction "2_2") (pintype "passive"))
    )
    (net (code "26") (name "HDMI_IN_TX_SCL") (class "Default")
      (node (ref "IC2") (pin "22") (pinfunction "TSCL_22") (pintype "bidirectional"))
      (node (ref "J1") (pin "52") (pinfunction "52_52") (pintype "passive"))
      (node (ref "R42") (pin "2") (pinfunction "2_2") (pintype "passive"))
    )
    (net (code "27") (name "HDMI_IN_TX_SDA") (class "Default")
      (node (ref "IC2") (pin "23") (pinfunction "TSDA_23") (pintype "bidirectional"))
      (node (ref "J1") (pin "53") (pinfunction "53_53") (pintype "passive"))
      (node (ref "R43") (pin "2") (pinfunction "2_2") (pintype "passive"))
    )
    (net (code "28") (name "HDMI_TX_5V") (class "Default")
      (node (ref "J2") (pin "18") (pinfunction "18_18") (pintype "passive"))
      (node (ref "R15") (pin "2") (pinfunction "2_2") (pintype "passive"))
      (node (ref "R18") (pin "2") (pinfunction "2_2") (pintype "passive"))
    )
    (net (code "29") (name "Net-(C1-Pad2)") (class "Default")
      (node (ref "C1") (pin "2") (pinfunction "2_2") (pintype "passive"))
      (node (ref "J2") (pin "S1") (pinfunction "S_S1") (pintype "passive"))
      (node (ref "J2") (pin "S2") (pinfunction "S_S2") (pintype "passive"))
      (node (ref "J2") (pin "S3") (pinfunction "S_S3") (pintype "passive"))
      (node (ref "J2") (pin "S4") (pinfunction "S_S4") (pintype "passive"))
      (node (ref "R13") (pin "1") (pinfunction "1_1") (pintype "passive"))
    )
    (net (code "30") (name "Net-(C14-Pad2)") (class "Default")
      (node (ref "C14") (pin "2") (pinfunction "2_2") (pintype "passive"))
      (node (ref "J4") (pin "S1") (pinfunction "S_S1") (pintype "passive"))
      (node (ref "J4") (pin "S2") (pinfunction "S_S2") (pintype "passive"))
      (node (ref "J4") (pin "S3") (pinfunction "S_S3") (pintype "passive"))
      (node (ref "J4") (pin "S4") (pinfunction "S_S4") (pintype "passive"))
      (node (ref "R33") (pin "1") (pinfunction "1_1") (pintype "passive"))
    )
    (net (code "31") (name "Net-(D1-PadA)") (class "Default")
      (node (ref "D1") (pin "A") (pinfunction "A_A") (pintype "passive"))
      (node (ref "R9") (pin "1") (pinfunction "1_1") (pintype "passive"))
    )
    (net (code "32") (name "Net-(D1-PadC)") (class "Default")
      (node (ref "D1") (pin "C") (pinfunction "C_C") (pintype "passive"))
      (node (ref "J2") (pin "13") (pinfunction "13_13") (pintype "passive"))
    )
    (net (code "33") (name "Net-(D2-PadA)") (class "Default")
      (node (ref "D2") (pin "A") (pinfunction "A_A") (pintype "passive"))
      (node (ref "R30") (pin "1") (pinfunction "1_1") (pintype "passive"))
    )
    (net (code "34") (name "Net-(D2-PadC)") (class "Default")
      (node (ref "D2") (pin "C") (pinfunction "C_C") (pintype "passive"))
      (node (ref "J4") (pin "13") (pinfunction "13_13") (pintype "passive"))
    )
    (net (code "35") (name "Net-(IC1-I2CEN)") (class "Default")
      (node (ref "IC1") (pin "5") (pinfunction "I2CEN_5") (pintype "bidirectional"))
      (node (ref "R6") (pin "2") (pinfunction "2_2") (pintype "passive"))
    )
    (net (code "36") (name "Net-(IC1-OVS)") (class "Default")
      (node (ref "IC1") (pin "25") (pinfunction "OVS_25") (pintype "bidirectional"))
      (node (ref "R19") (pin "2") (pinfunction "2_2") (pintype "passive"))
      (node (ref "R20") (pin "1") (pinfunction "1_1") (pintype "passive"))
    )
    (net (code "37") (name "Net-(IC1-VSADJ)") (class "Default")
      (node (ref "IC1") (pin "30") (pinfunction "VSADJ_30") (pintype "bidirectional"))
      (node (ref "R14") (pin "1") (pinfunction "1_1") (pintype "passive"))
    )
    (net (code "38") (name "Net-(IC1-~{OE})") (class "Default")
      (node (ref "IC1") (pin "6") (pinfunction "~{OE}_6") (pintype "bidirectional"))
      (node (ref "R5") (pin "2") (pinfunction "2_2") (pintype "passive"))
    )
    (net (code "39") (name "Net-(IC2-I2CEN)") (class "Default")
      (node (ref "IC2") (pin "5") (pinfunction "I2CEN_5") (pintype "bidirectional"))
      (node (ref "R39") (pin "2") (pinfunction "2_2") (pintype "passive"))
    )
    (net (code "40") (name "Net-(IC2-OVS)") (class "Default")
      (node (ref "IC2") (pin "25") (pinfunction "OVS_25") (pintype "bidirectional"))
      (node (ref "R37") (pin "2") (pinfunction "2_2") (pintype "passive"))
      (node (ref "R38") (pin "1") (pinfunction "1_1") (pintype "passive"))
    )
    (net (code "41") (name "Net-(IC2-VSADJ)") (class "Default")
      (node (ref "IC2") (pin "30") (pinfunction "VSADJ_30") (pintype "bidirectional"))
      (node (ref "R34") (pin "1") (pinfunction "1_1") (pintype "passive"))
    )
    (net (code "42") (name "Net-(IC2-~{OE})") (class "Default")
      (node (ref "IC2") (pin "6") (pinfunction "~{OE}_6") (pintype "bidirectional"))
      (node (ref "R29") (pin "2") (pinfunction "2_2") (pintype "passive"))
    )
    (net (code "43") (name "Net-(J1-Pad29)") (class "Default")
      (node (ref "J1") (pin "29") (pinfunction "29_29") (pintype "passive"))
      (node (ref "R1") (pin "2") (pinfunction "2_2") (pintype "passive"))
    )
    (net (code "44") (name "Net-(J1-Pad30)") (class "Default")
      (node (ref "J1") (pin "30") (pinfunction "30_30") (pintype "passive"))
      (node (ref "R1") (pin "1") (pinfunction "1_1") (pintype "passive"))
      (node (ref "R16") (pin "1") (pinfunction "1_1") (pintype "passive"))
      (node (ref "R2") (pin "1") (pinfunction "1_1") (pintype "passive"))
    )
    (net (code "45") (name "Net-(J1-Pad89)") (class "Default")
      (node (ref "J1") (pin "89") (pinfunction "89_89") (pintype "passive"))
      (node (ref "R3") (pin "2") (pinfunction "2_2") (pintype "passive"))
    )
    (net (code "46") (name "Net-(J1-Pad90)") (class "Default")
      (node (ref "J1") (pin "90") (pinfunction "90_90") (pintype "passive"))
      (node (ref "R17") (pin "1") (pinfunction "1_1") (pintype "passive"))
      (node (ref "R3") (pin "1") (pinfunction "1_1") (pintype "passive"))
      (node (ref "R4") (pin "1") (pinfunction "1_1") (pintype "passive"))
    )
    (net (code "47") (name "Net-(J2-Pad19)") (class "Default")
      (node (ref "J2") (pin "19") (pinfunction "19_19") (pintype "passive"))
      (node (ref "R10") (pin "2") (pinfunction "2_2") (pintype "passive"))
      (node (ref "R11") (pin "1") (pinfunction "1_1") (pintype "passive"))
    )
    (net (code "48") (name "Net-(LED1-PadA)") (class "Default")
      (node (ref "LED1") (pin "A") (pinfunction "A_A") (pintype "passive"))
      (node (ref "R44") (pin "2") (pinfunction "2_2") (pintype "passive"))
    )
    (net (code "49") (name "Net-(T1-G)") (class "Default")
      (node (ref "R11") (pin "2") (pinfunction "2_2") (pintype "passive"))
      (node (ref "T1") (pin "3") (pinfunction "G_3") (pintype "passive"))
    )
    (net (code "50") (name "Net-(T2-D)") (class "Default")
      (node (ref "J4") (pin "19") (pinfunction "19_19") (pintype "passive"))
      (node (ref "R31") (pin "1") (pinfunction "1_1") (pintype "passive"))
      (node (ref "T2") (pin "1") (pinfunction "D_1") (pintype "passive"))
    )
    (net (code "51") (name "Net-(T2-G)") (class "Default")
      (node (ref "LED1") (pin "C") (pinfunction "C_C") (pintype "passive"))
      (node (ref "R32") (pin "2") (pinfunction "2_2") (pintype "passive"))
      (node (ref "T2") (pin "3") (pinfunction "G_3") (pintype "passive"))
      (node (ref "T3") (pin "1") (pinfunction "D_1") (pintype "passive"))
    )
    (net (code "52") (name "PRE") (class "Default")
      (node (ref "IC1") (pin "7") (pinfunction "PRE_7") (pintype "bidirectional"))
      (node (ref "R7") (pin "1") (pinfunction "1_1") (pintype "passive"))
      (node (ref "R8") (pin "2") (pinfunction "2_2") (pintype "passive"))
    )
    (net (code "53") (name "RX0_N") (class "Default")
      (node (ref "IC1") (pin "35") (pinfunction "~{RX0}_35") (pintype "bidirectional"))
      (node (ref "J1") (pin "12") (pinfunction "12_12") (pintype "passive"))
    )
    (net (code "54") (name "RX0_P") (class "Default")
      (node (ref "IC1") (pin "36") (pinfunction "RX0_36") (pintype "bidirectional"))
      (node (ref "J1") (pin "11") (pinfunction "11_11") (pintype "passive"))
    )
    (net (code "55") (name "RX1_N") (class "Default")
      (node (ref "IC1") (pin "38") (pinfunction "~{RX1}_38") (pintype "bidirectional"))
      (node (ref "J1") (pin "9") (pinfunction "9_9") (pintype "passive"))
    )
    (net (code "56") (name "RX1_P") (class "Default")
      (node (ref "IC1") (pin "39") (pinfunction "RX1_39") (pintype "bidirectional"))
      (node (ref "J1") (pin "8") (pinfunction "8_8") (pintype "passive"))
    )
    (net (code "57") (name "RX2_N") (class "Default")
      (node (ref "IC1") (pin "1") (pinfunction "~{RX2}_1") (pintype "bidirectional"))
      (node (ref "J1") (pin "7") (pinfunction "7_7") (pintype "passive"))
    )
    (net (code "58") (name "RX2_P") (class "Default")
      (node (ref "IC1") (pin "2") (pinfunction "RX2_2") (pintype "bidirectional"))
      (node (ref "J1") (pin "6") (pinfunction "6_6") (pintype "passive"))
    )
    (net (code "59") (name "RXC_N") (class "Default")
      (node (ref "IC1") (pin "32") (pinfunction "~{RXC}_32") (pintype "bidirectional"))
      (node (ref "J1") (pin "14") (pinfunction "14_14") (pintype "passive"))
    )
    (net (code "60") (name "RXC_P") (class "Default")
      (node (ref "IC1") (pin "33") (pinfunction "RXC_33") (pintype "bidirectional"))
      (node (ref "J1") (pin "13") (pinfunction "13_13") (pintype "passive"))
    )
    (net (code "61") (name "RX_SCL") (class "Default")
      (node (ref "IC1") (pin "29") (pinfunction "RSCL_29") (pintype "bidirectional"))
      (node (ref "J1") (pin "20") (pinfunction "20_20") (pintype "passive"))
      (node (ref "R21") (pin "2") (pinfunction "2_2") (pintype "passive"))
    )
    (net (code "62") (name "RX_SDA") (class "Default")
      (node (ref "IC1") (pin "28") (pinfunction "RSDA_28") (pintype "bidirectional"))
      (node (ref "J1") (pin "21") (pinfunction "21_21") (pintype "passive"))
      (node (ref "R22") (pin "2") (pinfunction "2_2") (pintype "passive"))
    )
    (net (code "63") (name "TX0_N") (class "Default")
      (node (ref "IC1") (pin "16") (pinfunction "~{TX0}_16") (pintype "bidirectional"))
      (node (ref "J2") (pin "9") (pinfunction "9_9") (pintype "passive"))
    )
    (net (code "64") (name "TX0_P") (class "Default")
      (node (ref "IC1") (pin "15") (pinfunction "TX0_15") (pintype "bidirectional"))
      (node (ref "J2") (pin "7") (pinfunction "7_7") (pintype "passive"))
    )
    (net (code "65") (name "TX1_N") (class "Default")
      (node (ref "IC1") (pin "13") (pinfunction "~{TX1}_13") (pintype "bidirectional"))
      (node (ref "J2") (pin "6") (pinfunction "6_6") (pintype "passive"))
    )
    (net (code "66") (name "TX1_P") (class "Default")
      (node (ref "IC1") (pin "12") (pinfunction "TX1_12") (pintype "bidirectional"))
      (node (ref "J2") (pin "4") (pinfunction "4_4") (pintype "passive"))
    )
    (net (code "67") (name "TX2_N") (class "Default")
      (node (ref "IC1") (pin "10") (pinfunction "~{TX2}_10") (pintype "bidirectional"))
      (node (ref "J2") (pin "3") (pinfunction "3_3") (pintype "passive"))
    )
    (net (code "68") (name "TX2_P") (class "Default")
      (node (ref "IC1") (pin "9") (pinfunction "TX2_9") (pintype "bidirectional"))
      (node (ref "J2") (pin "1") (pinfunction "1_1") (pintype "passive"))
    )
    (net (code "69") (name "TXC_N") (class "Default")
      (node (ref "IC1") (pin "19") (pinfunction "~{TXC}_19") (pintype "bidirectional"))
      (node (ref "J2") (pin "12") (pinfunction "12_12") (pintype "passive"))
    )
    (net (code "70") (name "TXC_P") (class "Default")
      (node (ref "IC1") (pin "18") (pinfunction "TXC_18") (pintype "bidirectional"))
      (node (ref "J2") (pin "10") (pinfunction "10_10") (pintype "passive"))
    )
    (net (code "71") (name "TX_SCL") (class "Default")
      (node (ref "IC1") (pin "22") (pinfunction "TSCL_22") (pintype "bidirectional"))
      (node (ref "J2") (pin "15") (pinfunction "15_15") (pintype "passive"))
      (node (ref "R18") (pin "1") (pinfunction "1_1") (pintype "passive"))
    )
    (net (code "72") (name "TX_SDA") (class "Default")
      (node (ref "IC1") (pin "23") (pinfunction "TSDA_23") (pintype "bidirectional"))
      (node (ref "J2") (pin "16") (pinfunction "16_16") (pintype "passive"))
      (node (ref "R15") (pin "1") (pinfunction "1_1") (pintype "passive"))
    )
    (net (code "73") (name "unconnected-(J1-Pad2)") (class "Default")
      (node (ref "J1") (pin "2") (pinfunction "2_2") (pintype "passive"))
    )
    (net (code "74") (name "unconnected-(J1-Pad3)") (class "Default")
      (node (ref "J1") (pin "3") (pinfunction "3_3") (pintype "passive"))
    )
    (net (code "75") (name "unconnected-(J1-Pad4)") (class "Default")
      (node (ref "J1") (pin "4") (pinfunction "4_4") (pintype "passive"))
    )
    (net (code "76") (name "unconnected-(J1-Pad5)") (class "Default")
      (node (ref "J1") (pin "5") (pinfunction "5_5") (pintype "passive"))
    )
    (net (code "77") (name "unconnected-(J1-Pad15)") (class "Default")
      (node (ref "J1") (pin "15") (pinfunction "15_15") (pintype "passive"))
    )
    (net (code "78") (name "unconnected-(J1-Pad16)") (class "Default")
      (node (ref "J1") (pin "16") (pinfunction "16_16") (pintype "passive"))
    )
    (net (code "79") (name "unconnected-(J1-Pad17)") (class "Default")
      (node (ref "J1") (pin "17") (pinfunction "17_17") (pintype "passive"))
    )
    (net (code "80") (name "unconnected-(J1-Pad18)") (class "Default")
      (node (ref "J1") (pin "18") (pinfunction "18_18") (pintype "passive"))
    )
    (net (code "81") (name "unconnected-(J1-Pad22)") (class "Default")
      (node (ref "J1") (pin "22") (pinfunction "22_22") (pintype "passive"))
    )
    (net (code "82") (name "unconnected-(J1-Pad23)") (class "Default")
      (node (ref "J1") (pin "23") (pinfunction "23_23") (pintype "passive"))
    )
    (net (code "83") (name "unconnected-(J1-Pad24)") (class "Default")
      (node (ref "J1") (pin "24") (pinfunction "24_24") (pintype "passive"))
    )
    (net (code "84") (name "unconnected-(J1-Pad25)") (class "Default")
      (node (ref "J1") (pin "25") (pinfunction "25_25") (pintype "passive"))
    )
    (net (code "85") (name "unconnected-(J1-Pad27)") (class "Default")
      (node (ref "J1") (pin "27") (pinfunction "27_27") (pintype "passive"))
    )
    (net (code "86") (name "unconnected-(J1-Pad32)") (class "Default")
      (node (ref "J1") (pin "32") (pinfunction "32_32") (pintype "passive"))
    )
    (net (code "87") (name "unconnected-(J1-Pad34)") (class "Default")
      (node (ref "J1") (pin "34") (pinfunction "34_34") (pintype "passive"))
    )
    (net (code "88") (name "unconnected-(J1-Pad35)") (class "Default")
      (node (ref "J1") (pin "35") (pinfunction "35_35") (pintype "passive"))
    )
    (net (code "89") (name "unconnected-(J1-Pad36)") (class "Default")
      (node (ref "J1") (pin "36") (pinfunction "36_36") (pintype "passive"))
    )
    (net (code "90") (name "unconnected-(J1-Pad37)") (class "Default")
      (node (ref "J1") (pin "37") (pinfunction "37_37") (pintype "passive"))
    )
    (net (code "91") (name "unconnected-(J1-Pad38)") (class "Default")
      (node (ref "J1") (pin "38") (pinfunction "38_38") (pintype "passive"))
    )
    (net (code "92") (name "unconnected-(J1-Pad39)") (class "Default")
      (node (ref "J1") (pin "39") (pinfunction "39_39") (pintype "passive"))
    )
    (net (code "93") (name "unconnected-(J1-Pad49)") (class "Default")
      (node (ref "J1") (pin "49") (pinfunction "49_49") (pintype "passive"))
    )
    (net (code "94") (name "unconnected-(J1-Pad50)") (class "Default")
      (node (ref "J1") (pin "50") (pinfunction "50_50") (pintype "passive"))
    )
    (net (code "95") (name "unconnected-(J1-Pad54)") (class "Default")
      (node (ref "J1") (pin "54") (pinfunction "54_54") (pintype "passive"))
    )
    (net (code "96") (name "unconnected-(J1-Pad55)") (class "Default")
      (node (ref "J1") (pin "55") (pinfunction "55_55") (pintype "passive"))
    )
    (net (code "97") (name "unconnected-(J1-Pad56)") (class "Default")
      (node (ref "J1") (pin "56") (pinfunction "56_56") (pintype "passive"))
    )
    (net (code "98") (name "unconnected-(J1-Pad57)") (class "Default")
      (node (ref "J1") (pin "57") (pinfunction "57_57") (pintype "passive"))
    )
    (net (code "99") (name "unconnected-(J1-Pad59)") (class "Default")
      (node (ref "J1") (pin "59") (pinfunction "59_59") (pintype "passive"))
    )
    (net (code "100") (name "unconnected-(J1-Pad62)") (class "Default")
      (node (ref "J1") (pin "62") (pinfunction "62_62") (pintype "passive"))
    )
    (net (code "101") (name "unconnected-(J1-Pad63)") (class "Default")
      (node (ref "J1") (pin "63") (pinfunction "63_63") (pintype "passive"))
    )
    (net (code "102") (name "unconnected-(J1-Pad64)") (class "Default")
      (node (ref "J1") (pin "64") (pinfunction "64_64") (pintype "passive"))
    )
    (net (code "103") (name "unconnected-(J1-Pad65)") (class "Default")
      (node (ref "J1") (pin "65") (pinfunction "65_65") (pintype "passive"))
    )
    (net (code "104") (name "unconnected-(J1-Pad66)") (class "Default")
      (node (ref "J1") (pin "66") (pinfunction "66_66") (pintype "passive"))
    )
    (net (code "105") (name "unconnected-(J1-Pad67)") (class "Default")
      (node (ref "J1") (pin "67") (pinfunction "67_67") (pintype "passive"))
    )
    (net (code "106") (name "unconnected-(J1-Pad68)") (class "Default")
      (node (ref "J1") (pin "68") (pinfunction "68_68") (pintype "passive"))
    )
    (net (code "107") (name "unconnected-(J1-Pad69)") (class "Default")
      (node (ref "J1") (pin "69") (pinfunction "69_69") (pintype "passive"))
    )
    (net (code "108") (name "unconnected-(J1-Pad71)") (class "Default")
      (node (ref "J1") (pin "71") (pinfunction "71_71") (pintype "passive"))
    )
    (net (code "109") (name "unconnected-(J1-Pad72)") (class "Default")
      (node (ref "J1") (pin "72") (pinfunction "72_72") (pintype "passive"))
    )
    (net (code "110") (name "unconnected-(J1-Pad73)") (class "Default")
      (node (ref "J1") (pin "73") (pinfunction "73_73") (pintype "passive"))
    )
    (net (code "111") (name "unconnected-(J1-Pad74)") (class "Default")
      (node (ref "J1") (pin "74") (pinfunction "74_74") (pintype "passive"))
    )
    (net (code "112") (name "unconnected-(J1-Pad75)") (class "Default")
      (node (ref "J1") (pin "75") (pinfunction "75_75") (pintype "passive"))
    )
    (net (code "113") (name "unconnected-(J1-Pad76)") (class "Default")
      (node (ref "J1") (pin "76") (pinfunction "76_76") (pintype "passive"))
    )
    (net (code "114") (name "unconnected-(J1-Pad77)") (class "Default")
      (node (ref "J1") (pin "77") (pinfunction "77_77") (pintype "passive"))
    )
    (net (code "115") (name "unconnected-(J1-Pad78)") (class "Default")
      (node (ref "J1") (pin "78") (pinfunction "78_78") (pintype "passive"))
    )
    (net (code "116") (name "unconnected-(J1-Pad80)") (class "Default")
      (node (ref "J1") (pin "80") (pinfunction "80_80") (pintype "passive"))
    )
    (net (code "117") (name "unconnected-(J1-Pad81)") (class "Default")
      (node (ref "J1") (pin "81") (pinfunction "81_81") (pintype "passive"))
    )
    (net (code "118") (name "unconnected-(J1-Pad82)") (class "Default")
      (node (ref "J1") (pin "82") (pinfunction "82_82") (pintype "passive"))
    )
    (net (code "119") (name "unconnected-(J1-Pad83)") (class "Default")
      (node (ref "J1") (pin "83") (pinfunction "83_83") (pintype "passive"))
    )
    (net (code "120") (name "unconnected-(J1-Pad84)") (class "Default")
      (node (ref "J1") (pin "84") (pinfunction "84_84") (pintype "passive"))
    )
    (net (code "121") (name "unconnected-(J1-Pad85)") (class "Default")
      (node (ref "J1") (pin "85") (pinfunction "85_85") (pintype "passive"))
    )
    (net (code "122") (name "unconnected-(J1-Pad86)") (class "Default")
      (node (ref "J1") (pin "86") (pinfunction "86_86") (pintype "passive"))
    )
    (net (code "123") (name "unconnected-(J1-Pad87)") (class "Default")
      (node (ref "J1") (pin "87") (pinfunction "87_87") (pintype "passive"))
    )
    (net (code "124") (name "unconnected-(J1-Pad92)") (class "Default")
      (node (ref "J1") (pin "92") (pinfunction "92_92") (pintype "passive"))
    )
    (net (code "125") (name "unconnected-(J1-Pad94)") (class "Default")
      (node (ref "J1") (pin "94") (pinfunction "94_94") (pintype "passive"))
    )
    (net (code "126") (name "unconnected-(J1-Pad95)") (class "Default")
      (node (ref "J1") (pin "95") (pinfunction "95_95") (pintype "passive"))
    )
    (net (code "127") (name "unconnected-(J1-Pad96)") (class "Default")
      (node (ref "J1") (pin "96") (pinfunction "96_96") (pintype "passive"))
    )
    (net (code "128") (name "unconnected-(J1-Pad97)") (class "Default")
      (node (ref "J1") (pin "97") (pinfunction "97_97") (pintype "passive"))
    )
    (net (code "129") (name "unconnected-(J1-Pad98)") (class "Default")
      (node (ref "J1") (pin "98") (pinfunction "98_98") (pintype "passive"))
    )
    (net (code "130") (name "unconnected-(J1-Pad99)") (class "Default")
      (node (ref "J1") (pin "99") (pinfunction "99_99") (pintype "passive"))
    )
    (net (code "131") (name "unconnected-(J1-Pad100)") (class "Default")
      (node (ref "J1") (pin "100") (pinfunction "100_100") (pintype "passive"))
    )
    (net (code "132") (name "unconnected-(J1-Pad101)") (class "Default")
      (node (ref "J1") (pin "101") (pinfunction "101_101") (pintype "passive"))
    )
    (net (code "133") (name "unconnected-(J1-Pad103)") (class "Default")
      (node (ref "J1") (pin "103") (pinfunction "103_103") (pintype "passive"))
    )
    (net (code "134") (name "unconnected-(J1-Pad104)") (class "Default")
      (node (ref "J1") (pin "104") (pinfunction "104_104") (pintype "passive"))
    )
    (net (code "135") (name "unconnected-(J1-Pad105)") (class "Default")
      (node (ref "J1") (pin "105") (pinfunction "105_105") (pintype "passive"))
    )
    (net (code "136") (name "unconnected-(J1-Pad106)") (class "Default")
      (node (ref "J1") (pin "106") (pinfunction "106_106") (pintype "passive"))
    )
    (net (code "137") (name "unconnected-(J1-Pad107)") (class "Default")
      (node (ref "J1") (pin "107") (pinfunction "107_107") (pintype "passive"))
    )
    (net (code "138") (name "unconnected-(J1-Pad108)") (class "Default")
      (node (ref "J1") (pin "108") (pinfunction "108_108") (pintype "passive"))
    )
    (net (code "139") (name "unconnected-(J1-Pad109)") (class "Default")
      (node (ref "J1") (pin "109") (pinfunction "109_109") (pintype "passive"))
    )
    (net (code "140") (name "unconnected-(J1-Pad110)") (class "Default")
      (node (ref "J1") (pin "110") (pinfunction "110_110") (pintype "passive"))
    )
    (net (code "141") (name "unconnected-(J1-Pad112)") (class "Default")
      (node (ref "J1") (pin "112") (pinfunction "112_112") (pintype "passive"))
    )
    (net (code "142") (name "unconnected-(J1-Pad113)") (class "Default")
      (node (ref "J1") (pin "113") (pinfunction "113_113") (pintype "passive"))
    )
    (net (code "143") (name "unconnected-(J1-Pad114)") (class "Default")
      (node (ref "J1") (pin "114") (pinfunction "114_114") (pintype "passive"))
    )
    (net (code "144") (name "unconnected-(J1-Pad115)") (class "Default")
      (node (ref "J1") (pin "115") (pinfunction "115_115") (pintype "passive"))
    )
    (net (code "145") (name "unconnected-(J1-Pad116)") (class "Default")
      (node (ref "J1") (pin "116") (pinfunction "116_116") (pintype "passive"))
    )
    (net (code "146") (name "unconnected-(J1-Pad117)") (class "Default")
      (node (ref "J1") (pin "117") (pinfunction "117_117") (pintype "passive"))
    )
    (net (code "147") (name "unconnected-(J1-Pad118)") (class "Default")
      (node (ref "J1") (pin "118") (pinfunction "118_118") (pintype "passive"))
    )
    (net (code "148") (name "unconnected-(J1-Pad119)") (class "Default")
      (node (ref "J1") (pin "119") (pinfunction "119_119") (pintype "passive"))
    )
    (net (code "149") (name "unconnected-(J2-Pad14)") (class "Default")
      (node (ref "J2") (pin "14") (pinfunction "14_14") (pintype "passive"))
    )
    (net (code "150") (name "unconnected-(J4-Pad14)") (class "Default")
      (node (ref "J4") (pin "14") (pinfunction "14_14") (pintype "passive"))
    )
  )
)
